# BLEbee-2_0_0-REV-A.net
KiCad netlist of a schematic drawn in EAGLE
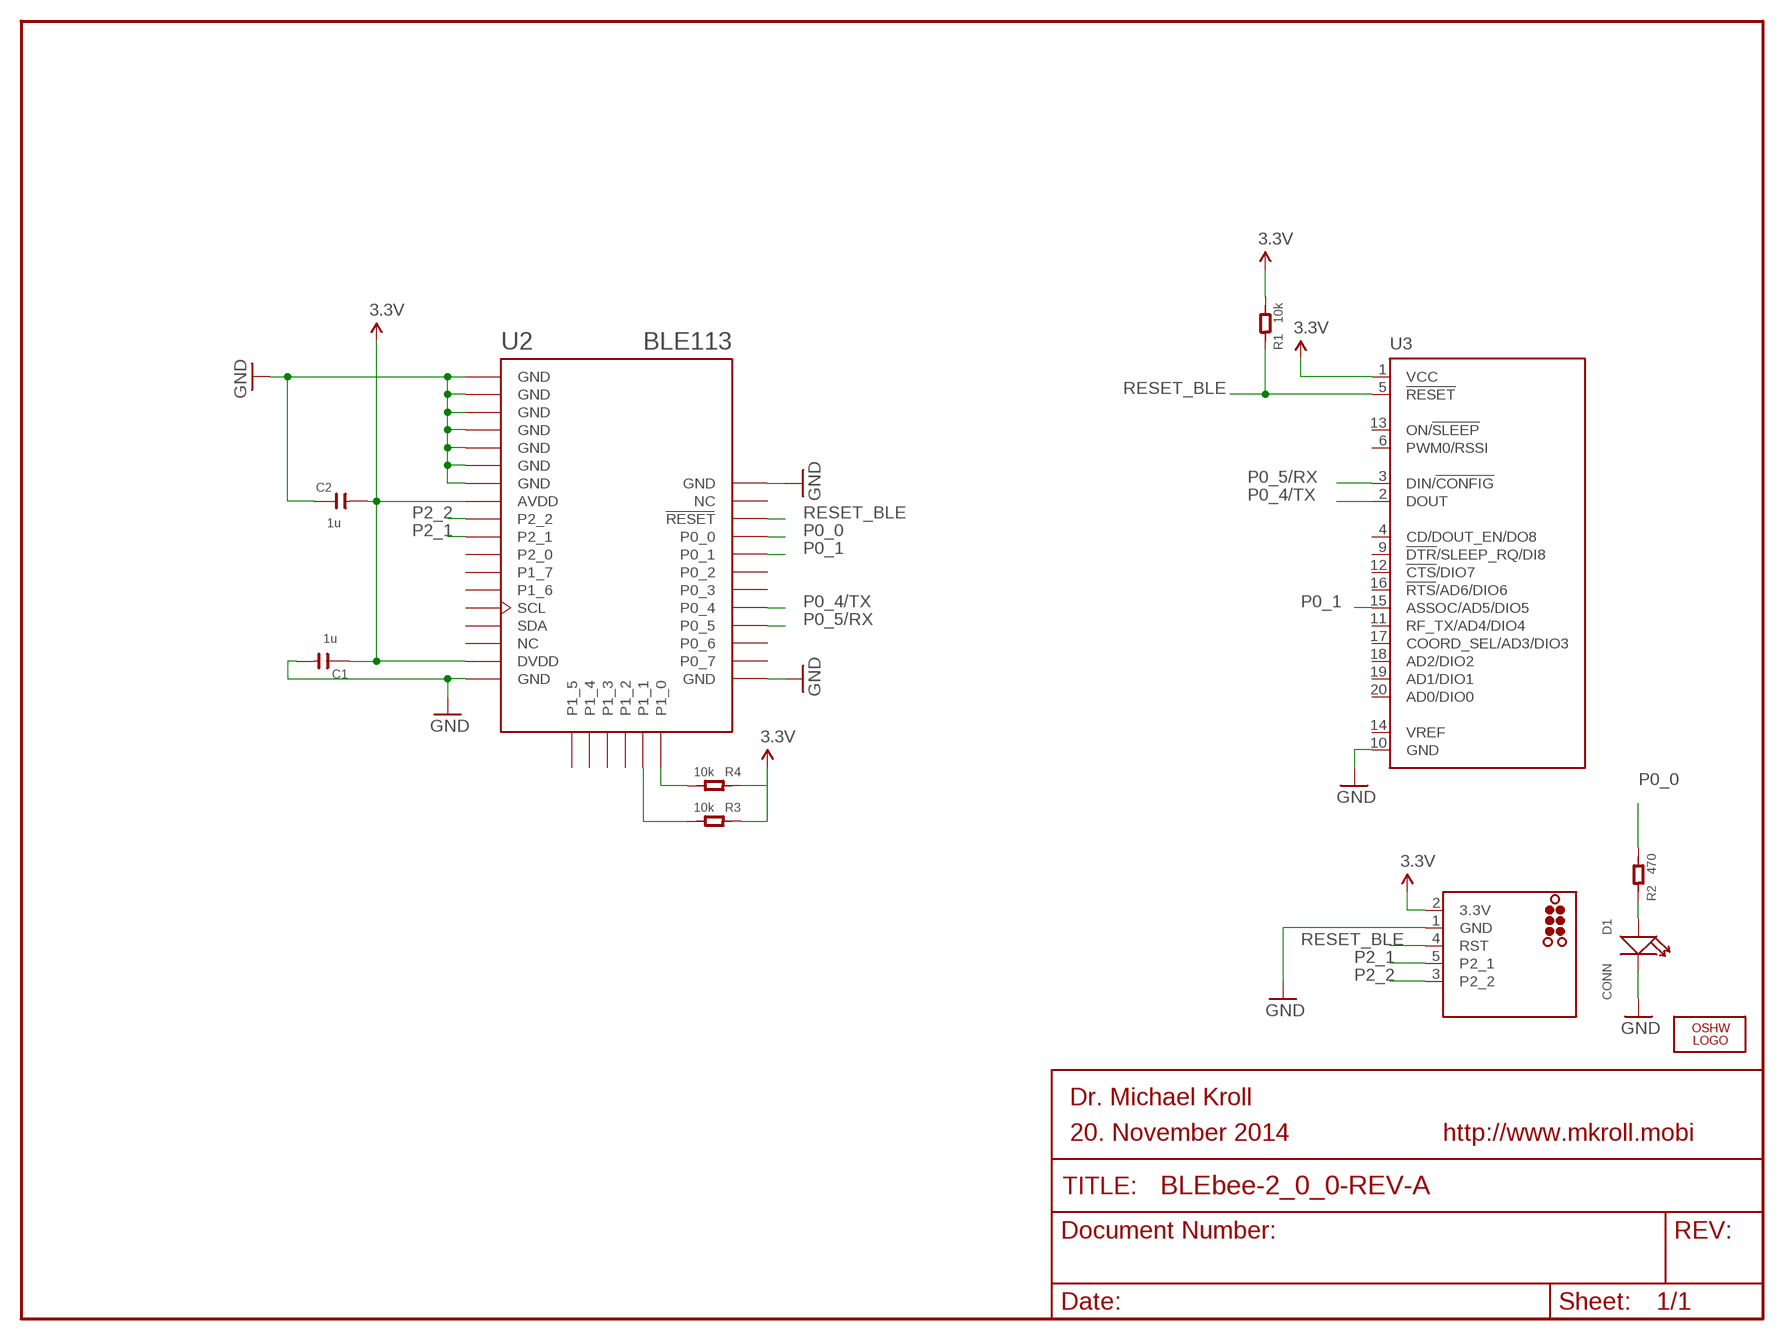
[diagram p0: schematic, sheet 1]

(export (version "E")
  (design (tool "Eeschema 10.0.6"))
  (components
    (comp (ref "C1")
      (value "1u")
      (footprint "eagle-import:C0603")
      (libsource (lib "eagle-import") (part "C-0603"))
    )
    (comp (ref "C2")
      (value "1u")
      (footprint "eagle-import:C0603")
      (libsource (lib "eagle-import") (part "C-0603"))
    )
    (comp (ref "D1")
      (value "CONN")
      (footprint "eagle-import:LED0603")
      (libsource (lib "eagle-import") (part "LED"))
    )
    (comp (ref "J1")
      (value "TC2030-CC-DEBUGGER")
      (footprint "eagle-import:TC2030-MCP-NL")
      (libsource (lib "eagle-import") (part "TC2030-CC-DEBUGGER"))
    )
    (comp (ref "LOGO1")
      (value "LOGO-OSHW-6MILX0100-NT")
      (footprint "eagle-import:OSHW_6X100_NOTEXT")
      (libsource (lib "eagle-import") (part "LOGO-OSHW-6MILX0100-NT"))
    )
    (comp (ref "R1")
      (value "10k")
      (footprint "eagle-import:R0603")
      (libsource (lib "eagle-import") (part "R-0603"))
    )
    (comp (ref "R2")
      (value "470")
      (footprint "eagle-import:R0603")
      (libsource (lib "eagle-import") (part "R-0603"))
    )
    (comp (ref "R3")
      (value "10k")
      (footprint "eagle-import:R0603")
      (libsource (lib "eagle-import") (part "R-0603"))
    )
    (comp (ref "R4")
      (value "10k")
      (footprint "eagle-import:R0603")
      (libsource (lib "eagle-import") (part "R-0603"))
    )
    (comp (ref "U2")
      (value "BLE113")
      (footprint "eagle-import:BLE113-A")
      (libsource (lib "eagle-import") (part "BLE113-A-VISUAL"))
    )
    (comp (ref "U3")
      (value "MODULE_BEE-XBEE-DIP")
      (footprint "eagle-import:MODULE_20P-DIP-2.0-W_-SILK")
      (libsource (lib "eagle-import") (part "MODULE_BEE-XBEE-DIP"))
    )
  )
  (nets
    (net (code "1") (name "/P0_0") (class "Default")
      (node (ref "R2") (pin "2") (pinfunction "2_2") (pintype "bidirectional"))
      (node (ref "U2") (pin "P0_0") (pinfunction "P0_0_P0_0") (pintype "bidirectional"))
    )
    (net (code "2") (name "/P0_1") (class "Default")
      (node (ref "U2") (pin "P0_1") (pinfunction "P0_1_P0_1") (pintype "bidirectional"))
      (node (ref "U3") (pin "15") (pinfunction "ASSOC/AD5/DIO5_15") (pintype "bidirectional"))
    )
    (net (code "3") (name "/P0_4{slash}TX") (class "Default")
      (node (ref "U2") (pin "P0_4") (pinfunction "P0_4_P0_4") (pintype "bidirectional"))
      (node (ref "U3") (pin "2") (pinfunction "DOUT_2") (pintype "output"))
    )
    (net (code "4") (name "/P0_5{slash}RX") (class "Default")
      (node (ref "U2") (pin "P0_5") (pinfunction "P0_5_P0_5") (pintype "bidirectional"))
      (node (ref "U3") (pin "3") (pinfunction "DIN/~{CONFIG}_3") (pintype "input"))
    )
    (net (code "5") (name "/P2_1") (class "Default")
      (node (ref "J1") (pin "5") (pinfunction "P2_1_5") (pintype "bidirectional"))
      (node (ref "U2") (pin "P2_1") (pinfunction "P2_1_P2_1") (pintype "bidirectional"))
    )
    (net (code "6") (name "/P2_2") (class "Default")
      (node (ref "J1") (pin "3") (pinfunction "P2_2_3") (pintype "bidirectional"))
      (node (ref "U2") (pin "P2_2") (pinfunction "P2_2_P2_2") (pintype "bidirectional"))
    )
    (net (code "7") (name "/RESET_BLE") (class "Default")
      (node (ref "J1") (pin "4") (pinfunction "RST_4") (pintype "bidirectional"))
      (node (ref "R1") (pin "1") (pinfunction "1_1") (pintype "bidirectional"))
      (node (ref "U2") (pin "RESET") (pinfunction "RESET_RESET") (pintype "input"))
      (node (ref "U3") (pin "5") (pinfunction "~{RESET}_5") (pintype "input"))
    )
    (net (code "8") (name "3.3V") (class "Default")
      (node (ref "C1") (pin "2") (pinfunction "2_2") (pintype "bidirectional"))
      (node (ref "C2") (pin "1") (pinfunction "1_1") (pintype "bidirectional"))
      (node (ref "J1") (pin "2") (pinfunction "3.3V_2") (pintype "power_in"))
      (node (ref "R1") (pin "2") (pinfunction "2_2") (pintype "bidirectional"))
      (node (ref "R3") (pin "1") (pinfunction "1_1") (pintype "bidirectional"))
      (node (ref "R4") (pin "1") (pinfunction "1_1") (pintype "bidirectional"))
      (node (ref "U2") (pin "AVDD") (pinfunction "AVDD_AVDD") (pintype "power_in"))
      (node (ref "U2") (pin "DVDD") (pinfunction "DVDD_DVDD") (pintype "power_in"))
      (node (ref "U3") (pin "1") (pinfunction "VCC_1") (pintype "power_in"))
    )
    (net (code "9") (name "GND") (class "Default")
      (node (ref "C1") (pin "1") (pinfunction "1_1") (pintype "bidirectional"))
      (node (ref "C2") (pin "2") (pinfunction "2_2") (pintype "bidirectional"))
      (node (ref "D1") (pin "-") (pinfunction "-_-") (pintype "passive"))
      (node (ref "J1") (pin "1") (pinfunction "GND_1") (pintype "power_in"))
      (node (ref "U2") (pin "GND") (pinfunction "GND_GND") (pintype "power_in"))
      (node (ref "U2") (pin "GND@10") (pinfunction "GND_GND@10") (pintype "power_in"))
      (node (ref "U2") (pin "GND@2") (pinfunction "GND_GND@2") (pintype "power_in"))
      (node (ref "U2") (pin "GND@3") (pinfunction "GND_GND@3") (pintype "power_in"))
      (node (ref "U2") (pin "GND@4") (pinfunction "GND_GND@4") (pintype "power_in"))
      (node (ref "U2") (pin "GND@5") (pinfunction "GND_GND@5") (pintype "power_in"))
      (node (ref "U2") (pin "GND@6") (pinfunction "GND_GND@6") (pintype "power_in"))
      (node (ref "U2") (pin "GND@7") (pinfunction "GND_GND@7") (pintype "power_in"))
      (node (ref "U2") (pin "GND@8") (pinfunction "GND_GND@8") (pintype "power_in"))
      (node (ref "U2") (pin "GND@9") (pinfunction "GND_GND@9") (pintype "power_in"))
      (node (ref "U3") (pin "10") (pinfunction "GND_10") (pintype "bidirectional"))
    )
    (net (code "10") (name "Net-(D1-Pad+)") (class "Default")
      (node (ref "D1") (pin "+") (pinfunction "+_+") (pintype "passive"))
      (node (ref "R2") (pin "1") (pinfunction "1_1") (pintype "bidirectional"))
    )
    (net (code "11") (name "Net-(R3-Pad2)") (class "Default")
      (node (ref "R3") (pin "2") (pinfunction "2_2") (pintype "bidirectional"))
      (node (ref "U2") (pin "P1_1") (pinfunction "P1_1_P1_1") (pintype "bidirectional"))
    )
    (net (code "12") (name "Net-(R4-Pad2)") (class "Default")
      (node (ref "R4") (pin "2") (pinfunction "2_2") (pintype "bidirectional"))
      (node (ref "U2") (pin "P1_0") (pinfunction "P1_0_P1_0") (pintype "bidirectional"))
    )
    (net (code "13") (name "unconnected-(U2-NC-PadNC@2)") (class "Default")
      (node (ref "U2") (pin "NC@2") (pinfunction "NC_NC@2") (pintype "no_connect"))
    )
    (net (code "14") (name "unconnected-(U2-PadNC)") (class "Default")
      (node (ref "U2") (pin "NC") (pinfunction "NC_NC") (pintype "no_connect"))
    )
    (net (code "15") (name "unconnected-(U2-PadP0_2)") (class "Default")
      (node (ref "U2") (pin "P0_2") (pinfunction "P0_2_P0_2") (pintype "bidirectional"))
    )
    (net (code "16") (name "unconnected-(U2-PadP0_3)") (class "Default")
      (node (ref "U2") (pin "P0_3") (pinfunction "P0_3_P0_3") (pintype "bidirectional"))
    )
    (net (code "17") (name "unconnected-(U2-PadP0_6)") (class "Default")
      (node (ref "U2") (pin "P0_6") (pinfunction "P0_6_P0_6") (pintype "bidirectional"))
    )
    (net (code "18") (name "unconnected-(U2-PadP0_7)") (class "Default")
      (node (ref "U2") (pin "P0_7") (pinfunction "P0_7_P0_7") (pintype "bidirectional"))
    )
    (net (code "19") (name "unconnected-(U2-PadP1_2)") (class "Default")
      (node (ref "U2") (pin "P1_2") (pinfunction "P1_2_P1_2") (pintype "bidirectional"))
    )
    (net (code "20") (name "unconnected-(U2-PadP1_3)") (class "Default")
      (node (ref "U2") (pin "P1_3") (pinfunction "P1_3_P1_3") (pintype "bidirectional"))
    )
    (net (code "21") (name "unconnected-(U2-PadP1_4)") (class "Default")
      (node (ref "U2") (pin "P1_4") (pinfunction "P1_4_P1_4") (pintype "bidirectional"))
    )
    (net (code "22") (name "unconnected-(U2-PadP1_5)") (class "Default")
      (node (ref "U2") (pin "P1_5") (pinfunction "P1_5_P1_5") (pintype "bidirectional"))
    )
    (net (code "23") (name "unconnected-(U2-PadP1_6)") (class "Default")
      (node (ref "U2") (pin "P1_6") (pinfunction "P1_6_P1_6") (pintype "bidirectional"))
    )
    (net (code "24") (name "unconnected-(U2-PadP1_7)") (class "Default")
      (node (ref "U2") (pin "P1_7") (pinfunction "P1_7_P1_7") (pintype "bidirectional"))
    )
    (net (code "25") (name "unconnected-(U2-PadP2_0)") (class "Default")
      (node (ref "U2") (pin "P2_0") (pinfunction "P2_0_P2_0") (pintype "bidirectional"))
    )
    (net (code "26") (name "unconnected-(U2-PadSCL)") (class "Default")
      (node (ref "U2") (pin "SCL") (pinfunction "SCL_SCL") (pintype "bidirectional"))
    )
    (net (code "27") (name "unconnected-(U2-PadSDA)") (class "Default")
      (node (ref "U2") (pin "SDA") (pinfunction "SDA_SDA") (pintype "bidirectional"))
    )
    (net (code "28") (name "unconnected-(U3-AD0{slash}DIO0-Pad20)") (class "Default")
      (node (ref "U3") (pin "20") (pinfunction "AD0/DIO0_20") (pintype "bidirectional"))
    )
    (net (code "29") (name "unconnected-(U3-AD1{slash}DIO1-Pad19)") (class "Default")
      (node (ref "U3") (pin "19") (pinfunction "AD1/DIO1_19") (pintype "bidirectional"))
    )
    (net (code "30") (name "unconnected-(U3-AD2{slash}DIO2-Pad18)") (class "Default")
      (node (ref "U3") (pin "18") (pinfunction "AD2/DIO2_18") (pintype "bidirectional"))
    )
    (net (code "31") (name "unconnected-(U3-CD{slash}DOUT_EN{slash}DO8-Pad4)") (class "Default")
      (node (ref "U3") (pin "4") (pinfunction "CD/DOUT_EN/DO8_4") (pintype "output"))
    )
    (net (code "32") (name "unconnected-(U3-COORD_SEL{slash}AD3{slash}DIO3-Pad17)") (class "Default")
      (node (ref "U3") (pin "17") (pinfunction "COORD_SEL/AD3/DIO3_17") (pintype "bidirectional"))
    )
    (net (code "33") (name "unconnected-(U3-ON{slash}~{SLEEP}-Pad13)") (class "Default")
      (node (ref "U3") (pin "13") (pinfunction "ON/~{SLEEP}_13") (pintype "output"))
    )
    (net (code "34") (name "unconnected-(U3-PWM0{slash}RSSI-Pad6)") (class "Default")
      (node (ref "U3") (pin "6") (pinfunction "PWM0/RSSI_6") (pintype "output"))
    )
    (net (code "35") (name "unconnected-(U3-RF_TX{slash}AD4{slash}DIO4-Pad11)") (class "Default")
      (node (ref "U3") (pin "11") (pinfunction "RF_TX/AD4/DIO4_11") (pintype "bidirectional"))
    )
    (net (code "36") (name "unconnected-(U3-VREF-Pad14)") (class "Default")
      (node (ref "U3") (pin "14") (pinfunction "VREF_14") (pintype "input"))
    )
    (net (code "37") (name "unconnected-(U3-~{CTS}{slash}DIO7-Pad12)") (class "Default")
      (node (ref "U3") (pin "12") (pinfunction "~{CTS}/DIO7_12") (pintype "bidirectional"))
    )
    (net (code "38") (name "unconnected-(U3-~{DTR}{slash}SLEEP_RQ{slash}DI8-Pad9)") (class "Default")
      (node (ref "U3") (pin "9") (pinfunction "~{DTR}/SLEEP_RQ/DI8_9") (pintype "bidirectional"))
    )
    (net (code "39") (name "unconnected-(U3-~{RTS}{slash}AD6{slash}DIO6-Pad16)") (class "Default")
      (node (ref "U3") (pin "16") (pinfunction "~{RTS}/AD6/DIO6_16") (pintype "bidirectional"))
    )
  )
)
